# Communication_Part1.net
KiCad netlist of a schematic drawn in Altium Designer
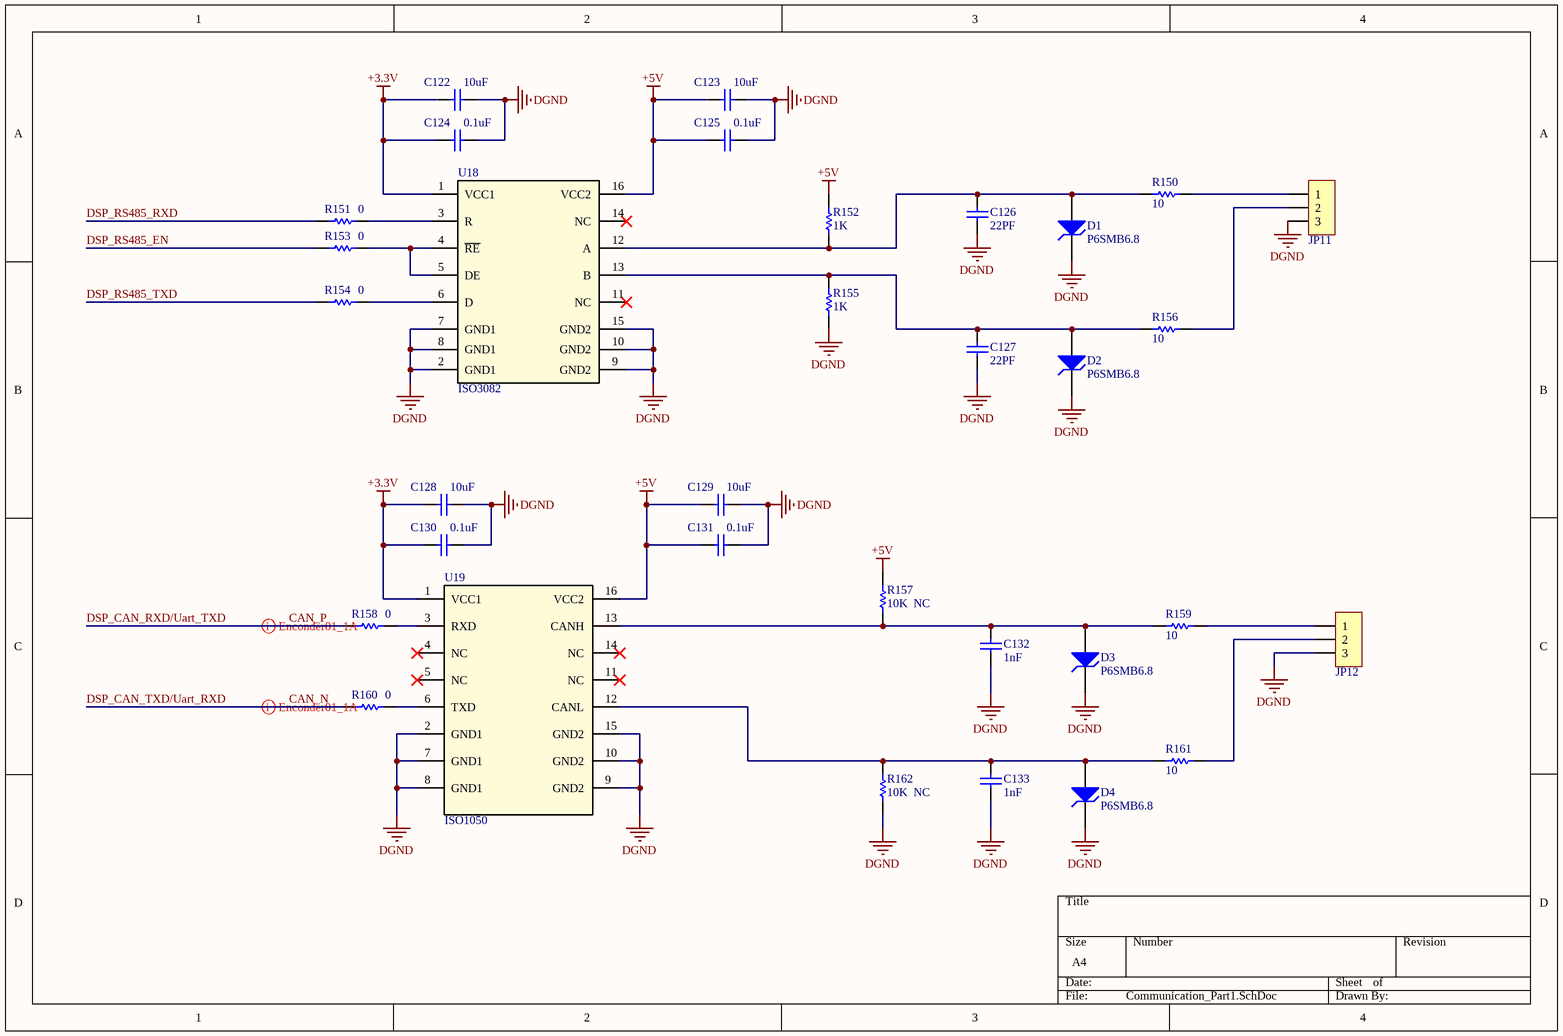
[diagram p0: Communication_Part1.SchDoc]

(export (version "E")
  (design (tool "Eeschema 10.0.6"))
  (components
    (comp (ref "C122")
      (value "10uF")
      (footprint "1608[0603]")
      (description "Capacitor")
      (fields (field (name "Comment") "Cap") (field (name "PUBLISHER") "Altium Limited"))
      (libsource (lib "Miscellaneous Devices") (part "Cap"))
    )
    (comp (ref "C123")
      (value "10uF")
      (footprint "1608[0603]")
      (description "Capacitor")
      (fields (field (name "Comment") "Cap") (field (name "PUBLISHER") "Altium Limited"))
      (libsource (lib "Miscellaneous Devices") (part "Cap"))
    )
    (comp (ref "C124")
      (value "0.1uF")
      (footprint "1608[0603]")
      (description "Capacitor")
      (fields (field (name "Comment") "Cap") (field (name "PUBLISHER") "Altium Limited"))
      (libsource (lib "Miscellaneous Devices") (part "Cap"))
    )
    (comp (ref "C125")
      (value "0.1uF")
      (footprint "1608[0603]")
      (description "Capacitor")
      (fields (field (name "Comment") "Cap") (field (name "PUBLISHER") "Altium Limited"))
      (libsource (lib "Miscellaneous Devices") (part "Cap"))
    )
    (comp (ref "C126")
      (value "22PF")
      (footprint "1608[0603]")
      (description "Capacitor")
      (fields (field (name "Comment") "Cap") (field (name "PUBLISHER") "Altium Limited"))
      (libsource (lib "Miscellaneous Devices") (part "Cap"))
    )
    (comp (ref "C127")
      (value "22PF")
      (footprint "1608[0603]")
      (description "Capacitor")
      (fields (field (name "Comment") "Cap") (field (name "PUBLISHER") "Altium Limited"))
      (libsource (lib "Miscellaneous Devices") (part "Cap"))
    )
    (comp (ref "C128")
      (value "10uF")
      (footprint "1608[0603]")
      (description "Capacitor")
      (fields (field (name "Comment") "Cap") (field (name "PUBLISHER") "Altium Limited"))
      (libsource (lib "Miscellaneous Devices") (part "Cap"))
    )
    (comp (ref "C129")
      (value "10uF")
      (footprint "1608[0603]")
      (description "Capacitor")
      (fields (field (name "Comment") "Cap") (field (name "PUBLISHER") "Altium Limited"))
      (libsource (lib "Miscellaneous Devices") (part "Cap"))
    )
    (comp (ref "C130")
      (value "0.1uF")
      (footprint "1608[0603]")
      (description "Capacitor")
      (fields (field (name "Comment") "Cap") (field (name "PUBLISHER") "Altium Limited"))
      (libsource (lib "Miscellaneous Devices") (part "Cap"))
    )
    (comp (ref "C131")
      (value "0.1uF")
      (footprint "1608[0603]")
      (description "Capacitor")
      (fields (field (name "Comment") "Cap") (field (name "PUBLISHER") "Altium Limited"))
      (libsource (lib "Miscellaneous Devices") (part "Cap"))
    )
    (comp (ref "C132")
      (value "1nF")
      (footprint "1608[0603]")
      (description "Capacitor")
      (fields (field (name "Comment") "Cap") (field (name "PUBLISHER") "Altium Limited"))
      (libsource (lib "Miscellaneous Devices") (part "Cap"))
    )
    (comp (ref "C133")
      (value "1nF")
      (footprint "1608[0603]")
      (description "Capacitor")
      (fields (field (name "Comment") "Cap") (field (name "PUBLISHER") "Altium Limited"))
      (libsource (lib "Miscellaneous Devices") (part "Cap"))
    )
    (comp (ref "D1")
      (value "P6SMB6.8")
      (footprint "DIODE_SMC")
      (description "Surface Mount Silicon Zener Diode")
      (fields (field (name "PUBLISHER") "Altium Limited"))
      (libsource (lib "Motorola Discrete Diode") (part "MMSZ56T1"))
    )
    (comp (ref "D2")
      (value "P6SMB6.8")
      (footprint "DIODE_SMC")
      (description "Surface Mount Silicon Zener Diode")
      (fields (field (name "PUBLISHER") "Altium Limited"))
      (libsource (lib "Motorola Discrete Diode") (part "MMSZ56T1"))
    )
    (comp (ref "D3")
      (value "P6SMB6.8")
      (footprint "DIODE_SMC")
      (description "Surface Mount Silicon Zener Diode")
      (fields (field (name "PUBLISHER") "Altium Limited"))
      (libsource (lib "Motorola Discrete Diode") (part "MMSZ56T1"))
    )
    (comp (ref "D4")
      (value "P6SMB6.8")
      (footprint "DIODE_SMC")
      (description "Surface Mount Silicon Zener Diode")
      (fields (field (name "PUBLISHER") "Altium Limited"))
      (libsource (lib "Motorola Discrete Diode") (part "MMSZ56T1"))
    )
    (comp (ref "JP11")
      (value "HDR-1X3")
      (footprint "ZH1.5-WI-3P")
      (description "3P接插件")
      (fields (field (name "版权归属") "源创客"))
      (libsource (lib "4.3   - 接插件-脚距1.5") (part "Header 3"))
    )
    (comp (ref "JP12")
      (value "HDR-1X3")
      (footprint "ZH1.5-WI-3P")
      (description "3P接插件")
      (fields (field (name "版权归属") "源创客"))
      (libsource (lib "4.3   - 接插件-脚距1.5") (part "Header 3"))
    )
    (comp (ref "R150")
      (value "10")
      (footprint "1608[0603]")
      (description "Resistor")
      (fields (field (name "Comment") "Res1") (field (name "PUBLISHER") "Altium Limited"))
      (libsource (lib "Miscellaneous Devices") (part "Res1"))
    )
    (comp (ref "R151")
      (value "0")
      (footprint "1608[0603]")
      (description "Resistor")
      (fields (field (name "Comment") "Res1") (field (name "PUBLISHER") "Altium Limited"))
      (libsource (lib "Miscellaneous Devices") (part "Res1"))
    )
    (comp (ref "R152")
      (value "1K")
      (footprint "1608[0603]")
      (description "Resistor")
      (fields (field (name "Comment") "Res1") (field (name "PUBLISHER") "Altium Limited"))
      (libsource (lib "Miscellaneous Devices") (part "Res1"))
    )
    (comp (ref "R153")
      (value "0")
      (footprint "1608[0603]")
      (description "Resistor")
      (fields (field (name "Comment") "Res1") (field (name "PUBLISHER") "Altium Limited"))
      (libsource (lib "Miscellaneous Devices") (part "Res1"))
    )
    (comp (ref "R154")
      (value "0")
      (footprint "1608[0603]")
      (description "Resistor")
      (fields (field (name "Comment") "Res1") (field (name "PUBLISHER") "Altium Limited"))
      (libsource (lib "Miscellaneous Devices") (part "Res1"))
    )
    (comp (ref "R155")
      (value "1K")
      (footprint "1608[0603]")
      (description "Resistor")
      (fields (field (name "Comment") "Res1") (field (name "PUBLISHER") "Altium Limited"))
      (libsource (lib "Miscellaneous Devices") (part "Res1"))
    )
    (comp (ref "R156")
      (value "10")
      (footprint "1608[0603]")
      (description "Resistor")
      (fields (field (name "Comment") "Res1") (field (name "PUBLISHER") "Altium Limited"))
      (libsource (lib "Miscellaneous Devices") (part "Res1"))
    )
    (comp (ref "R157")
      (value "10K  NC")
      (footprint "1608[0603]")
      (description "Resistor")
      (fields (field (name "Comment") "Res1") (field (name "PUBLISHER") "Altium Limited"))
      (libsource (lib "Miscellaneous Devices") (part "Res1"))
    )
    (comp (ref "R158")
      (value "0")
      (footprint "1608[0603]")
      (description "Resistor")
      (fields (field (name "Comment") "Res1") (field (name "PUBLISHER") "Altium Limited"))
      (libsource (lib "Miscellaneous Devices") (part "Res1"))
    )
    (comp (ref "R159")
      (value "10")
      (footprint "1608[0603]")
      (description "Resistor")
      (fields (field (name "Comment") "Res1") (field (name "PUBLISHER") "Altium Limited"))
      (libsource (lib "Miscellaneous Devices") (part "Res1"))
    )
    (comp (ref "R160")
      (value "0")
      (footprint "1608[0603]")
      (description "Resistor")
      (fields (field (name "Comment") "Res1") (field (name "PUBLISHER") "Altium Limited"))
      (libsource (lib "Miscellaneous Devices") (part "Res1"))
    )
    (comp (ref "R161")
      (value "10")
      (footprint "1608[0603]")
      (description "Resistor")
      (fields (field (name "Comment") "Res1") (field (name "PUBLISHER") "Altium Limited"))
      (libsource (lib "Miscellaneous Devices") (part "Res1"))
    )
    (comp (ref "R162")
      (value "10K  NC")
      (footprint "1608[0603]")
      (description "Resistor")
      (fields (field (name "Comment") "Res1") (field (name "PUBLISHER") "Altium Limited"))
      (libsource (lib "Miscellaneous Devices") (part "Res1"))
    )
    (comp (ref "U18")
      (value "ISO3082")
      (footprint "ISO3082_SOIC")
      (fields
        (field (name "MANUFACTURER") "Texas Instruments")
        (field (name "MANUFACTURER_PART_NUMBER") "iso3082_dw_16")
      )
      (libsource (lib "DSP_FPGA_Lib") (part "ISO3082"))
    )
    (comp (ref "U19")
      (value "ISO1050")
      (footprint "ISO1050_SOIC")
      (fields
        (field (name "MANUFACTURER") "Texas Instruments")
        (field (name "MANUFACTURER_PART_NUMBER") "iso1050_dw_16")
      )
      (libsource (lib "DSP_FPGA_Lib") (part "ISO1050"))
    )
  )
  (nets
    (net (code "1") (name "+3.3V") (class "Default")
      (node (ref "C122") (pin "2") (pinfunction "2_2") (pintype "passive"))
      (node (ref "C124") (pin "2") (pinfunction "2_2") (pintype "passive"))
      (node (ref "C128") (pin "2") (pinfunction "2_2") (pintype "passive"))
      (node (ref "C130") (pin "2") (pinfunction "2_2") (pintype "passive"))
      (node (ref "U18") (pin "1") (pinfunction "VCC1_1") (pintype "power_in"))
      (node (ref "U19") (pin "1") (pinfunction "VCC1_1") (pintype "power_in"))
    )
    (net (code "2") (name "+5V") (class "Default")
      (node (ref "C123") (pin "2") (pinfunction "2_2") (pintype "passive"))
      (node (ref "C125") (pin "2") (pinfunction "2_2") (pintype "passive"))
      (node (ref "C129") (pin "2") (pinfunction "2_2") (pintype "passive"))
      (node (ref "C131") (pin "2") (pinfunction "2_2") (pintype "passive"))
      (node (ref "R152") (pin "2") (pinfunction "2_2") (pintype "passive"))
      (node (ref "R157") (pin "2") (pinfunction "2_2") (pintype "passive"))
      (node (ref "U18") (pin "16") (pinfunction "VCC2_16") (pintype "power_in"))
      (node (ref "U19") (pin "16") (pinfunction "VCC2_16") (pintype "power_in"))
    )
    (net (code "3") (name "/CAN_N") (class "Default")
      (node (ref "R160") (pin "1") (pinfunction "1_1") (pintype "passive"))
    )
    (net (code "4") (name "/CAN_P") (class "Default")
      (node (ref "R158") (pin "1") (pinfunction "1_1") (pintype "passive"))
    )
    (net (code "5") (name "/DSP_RS485_EN") (class "Default")
      (node (ref "R153") (pin "1") (pinfunction "1_1") (pintype "passive"))
    )
    (net (code "6") (name "/DSP_RS485_RXD") (class "Default")
      (node (ref "R151") (pin "1") (pinfunction "1_1") (pintype "passive"))
    )
    (net (code "7") (name "/DSP_RS485_TXD") (class "Default")
      (node (ref "R154") (pin "1") (pinfunction "1_1") (pintype "passive"))
    )
    (net (code "8") (name "DGND") (class "Default")
      (node (ref "C122") (pin "1") (pinfunction "1_1") (pintype "passive"))
      (node (ref "C123") (pin "1") (pinfunction "1_1") (pintype "passive"))
      (node (ref "C124") (pin "1") (pinfunction "1_1") (pintype "passive"))
      (node (ref "C125") (pin "1") (pinfunction "1_1") (pintype "passive"))
      (node (ref "C126") (pin "2") (pinfunction "2_2") (pintype "passive"))
      (node (ref "C127") (pin "2") (pinfunction "2_2") (pintype "passive"))
      (node (ref "C128") (pin "1") (pinfunction "1_1") (pintype "passive"))
      (node (ref "C129") (pin "1") (pinfunction "1_1") (pintype "passive"))
      (node (ref "C130") (pin "1") (pinfunction "1_1") (pintype "passive"))
      (node (ref "C131") (pin "1") (pinfunction "1_1") (pintype "passive"))
      (node (ref "C132") (pin "2") (pinfunction "2_2") (pintype "passive"))
      (node (ref "C133") (pin "2") (pinfunction "2_2") (pintype "passive"))
      (node (ref "D1") (pin "1") (pinfunction "K_1") (pintype "passive"))
      (node (ref "D2") (pin "1") (pinfunction "K_1") (pintype "passive"))
      (node (ref "D3") (pin "1") (pinfunction "K_1") (pintype "passive"))
      (node (ref "D4") (pin "1") (pinfunction "K_1") (pintype "passive"))
      (node (ref "JP11") (pin "3") (pinfunction "3_3") (pintype "passive"))
      (node (ref "JP12") (pin "3") (pinfunction "3_3") (pintype "passive"))
      (node (ref "R155") (pin "1") (pinfunction "1_1") (pintype "passive"))
      (node (ref "R162") (pin "1") (pinfunction "1_1") (pintype "passive"))
      (node (ref "U18") (pin "10") (pinfunction "GND2_10") (pintype "power_in"))
      (node (ref "U18") (pin "15") (pinfunction "GND2_15") (pintype "power_in"))
      (node (ref "U18") (pin "2") (pinfunction "GND1_2") (pintype "power_in"))
      (node (ref "U18") (pin "7") (pinfunction "GND1_7") (pintype "power_in"))
      (node (ref "U18") (pin "8") (pinfunction "GND1_8") (pintype "power_in"))
      (node (ref "U18") (pin "9") (pinfunction "GND2_9") (pintype "power_in"))
      (node (ref "U19") (pin "10") (pinfunction "GND2_10") (pintype "power_in"))
      (node (ref "U19") (pin "15") (pinfunction "GND2_15") (pintype "power_in"))
      (node (ref "U19") (pin "2") (pinfunction "GND1_2") (pintype "power_in"))
      (node (ref "U19") (pin "7") (pinfunction "GND1_7") (pintype "power_in"))
      (node (ref "U19") (pin "8") (pinfunction "GND1_8") (pintype "power_in"))
      (node (ref "U19") (pin "9") (pinfunction "GND2_9") (pintype "power_in"))
    )
    (net (code "9") (name "Net-(D1-A)") (class "Default")
      (node (ref "C126") (pin "1") (pinfunction "1_1") (pintype "passive"))
      (node (ref "D1") (pin "2") (pinfunction "A_2") (pintype "passive"))
      (node (ref "R150") (pin "2") (pinfunction "2_2") (pintype "passive"))
      (node (ref "R152") (pin "1") (pinfunction "1_1") (pintype "passive"))
      (node (ref "U18") (pin "12") (pinfunction "A_12") (pintype "passive"))
    )
    (net (code "10") (name "Net-(D2-A)") (class "Default")
      (node (ref "C127") (pin "1") (pinfunction "1_1") (pintype "passive"))
      (node (ref "D2") (pin "2") (pinfunction "A_2") (pintype "passive"))
      (node (ref "R155") (pin "2") (pinfunction "2_2") (pintype "passive"))
      (node (ref "R156") (pin "2") (pinfunction "2_2") (pintype "passive"))
      (node (ref "U18") (pin "13") (pinfunction "B_13") (pintype "passive"))
    )
    (net (code "11") (name "Net-(D3-A)") (class "Default")
      (node (ref "C132") (pin "1") (pinfunction "1_1") (pintype "passive"))
      (node (ref "D3") (pin "2") (pinfunction "A_2") (pintype "passive"))
      (node (ref "R157") (pin "1") (pinfunction "1_1") (pintype "passive"))
      (node (ref "R159") (pin "2") (pinfunction "2_2") (pintype "passive"))
      (node (ref "U19") (pin "13") (pinfunction "CANH_13") (pintype "passive"))
    )
    (net (code "12") (name "Net-(D4-A)") (class "Default")
      (node (ref "C133") (pin "1") (pinfunction "1_1") (pintype "passive"))
      (node (ref "D4") (pin "2") (pinfunction "A_2") (pintype "passive"))
      (node (ref "R161") (pin "2") (pinfunction "2_2") (pintype "passive"))
      (node (ref "R162") (pin "2") (pinfunction "2_2") (pintype "passive"))
      (node (ref "U19") (pin "12") (pinfunction "CANL_12") (pintype "passive"))
    )
    (net (code "13") (name "Net-(JP11-Pad1)") (class "Default")
      (node (ref "JP11") (pin "1") (pinfunction "1_1") (pintype "passive"))
      (node (ref "R150") (pin "1") (pinfunction "1_1") (pintype "passive"))
    )
    (net (code "14") (name "Net-(JP11-Pad2)") (class "Default")
      (node (ref "JP11") (pin "2") (pinfunction "2_2") (pintype "passive"))
      (node (ref "R156") (pin "1") (pinfunction "1_1") (pintype "passive"))
    )
    (net (code "15") (name "Net-(JP12-Pad1)") (class "Default")
      (node (ref "JP12") (pin "1") (pinfunction "1_1") (pintype "passive"))
      (node (ref "R159") (pin "1") (pinfunction "1_1") (pintype "passive"))
    )
    (net (code "16") (name "Net-(JP12-Pad2)") (class "Default")
      (node (ref "JP12") (pin "2") (pinfunction "2_2") (pintype "passive"))
      (node (ref "R161") (pin "1") (pinfunction "1_1") (pintype "passive"))
    )
    (net (code "17") (name "Net-(U18-D)") (class "Default")
      (node (ref "R154") (pin "2") (pinfunction "2_2") (pintype "passive"))
      (node (ref "U18") (pin "6") (pinfunction "D_6") (pintype "passive"))
    )
    (net (code "18") (name "Net-(U18-DE)") (class "Default")
      (node (ref "R153") (pin "2") (pinfunction "2_2") (pintype "passive"))
      (node (ref "U18") (pin "4") (pinfunction "~{RE}_4") (pintype "passive"))
      (node (ref "U18") (pin "5") (pinfunction "DE_5") (pintype "passive"))
    )
    (net (code "19") (name "Net-(U18-R)") (class "Default")
      (node (ref "R151") (pin "2") (pinfunction "2_2") (pintype "passive"))
      (node (ref "U18") (pin "3") (pinfunction "R_3") (pintype "passive"))
    )
    (net (code "20") (name "Net-(U19-RXD)") (class "Default")
      (node (ref "R158") (pin "2") (pinfunction "2_2") (pintype "passive"))
      (node (ref "U19") (pin "3") (pinfunction "RXD_3") (pintype "passive"))
    )
    (net (code "21") (name "Net-(U19-TXD)") (class "Default")
      (node (ref "R160") (pin "2") (pinfunction "2_2") (pintype "passive"))
      (node (ref "U19") (pin "6") (pinfunction "TXD_6") (pintype "passive"))
    )
    (net (code "22") (name "unconnected-(U18-NC-Pad11)") (class "Default")
      (node (ref "U18") (pin "11") (pinfunction "NC_11") (pintype "passive+no_connect"))
    )
    (net (code "23") (name "unconnected-(U18-NC-Pad14)") (class "Default")
      (node (ref "U18") (pin "14") (pinfunction "NC_14") (pintype "passive+no_connect"))
    )
    (net (code "24") (name "unconnected-(U19-NC-Pad4)") (class "Default")
      (node (ref "U19") (pin "4") (pinfunction "NC_4") (pintype "passive+no_connect"))
    )
    (net (code "25") (name "unconnected-(U19-NC-Pad5)") (class "Default")
      (node (ref "U19") (pin "5") (pinfunction "NC_5") (pintype "passive+no_connect"))
    )
    (net (code "26") (name "unconnected-(U19-NC-Pad11)") (class "Default")
      (node (ref "U19") (pin "11") (pinfunction "NC_11") (pintype "passive+no_connect"))
    )
    (net (code "27") (name "unconnected-(U19-NC-Pad14)") (class "Default")
      (node (ref "U19") (pin "14") (pinfunction "NC_14") (pintype "passive+no_connect"))
    )
  )
)
